# Power.net
KiCad netlist of a schematic drawn in Altium Designer
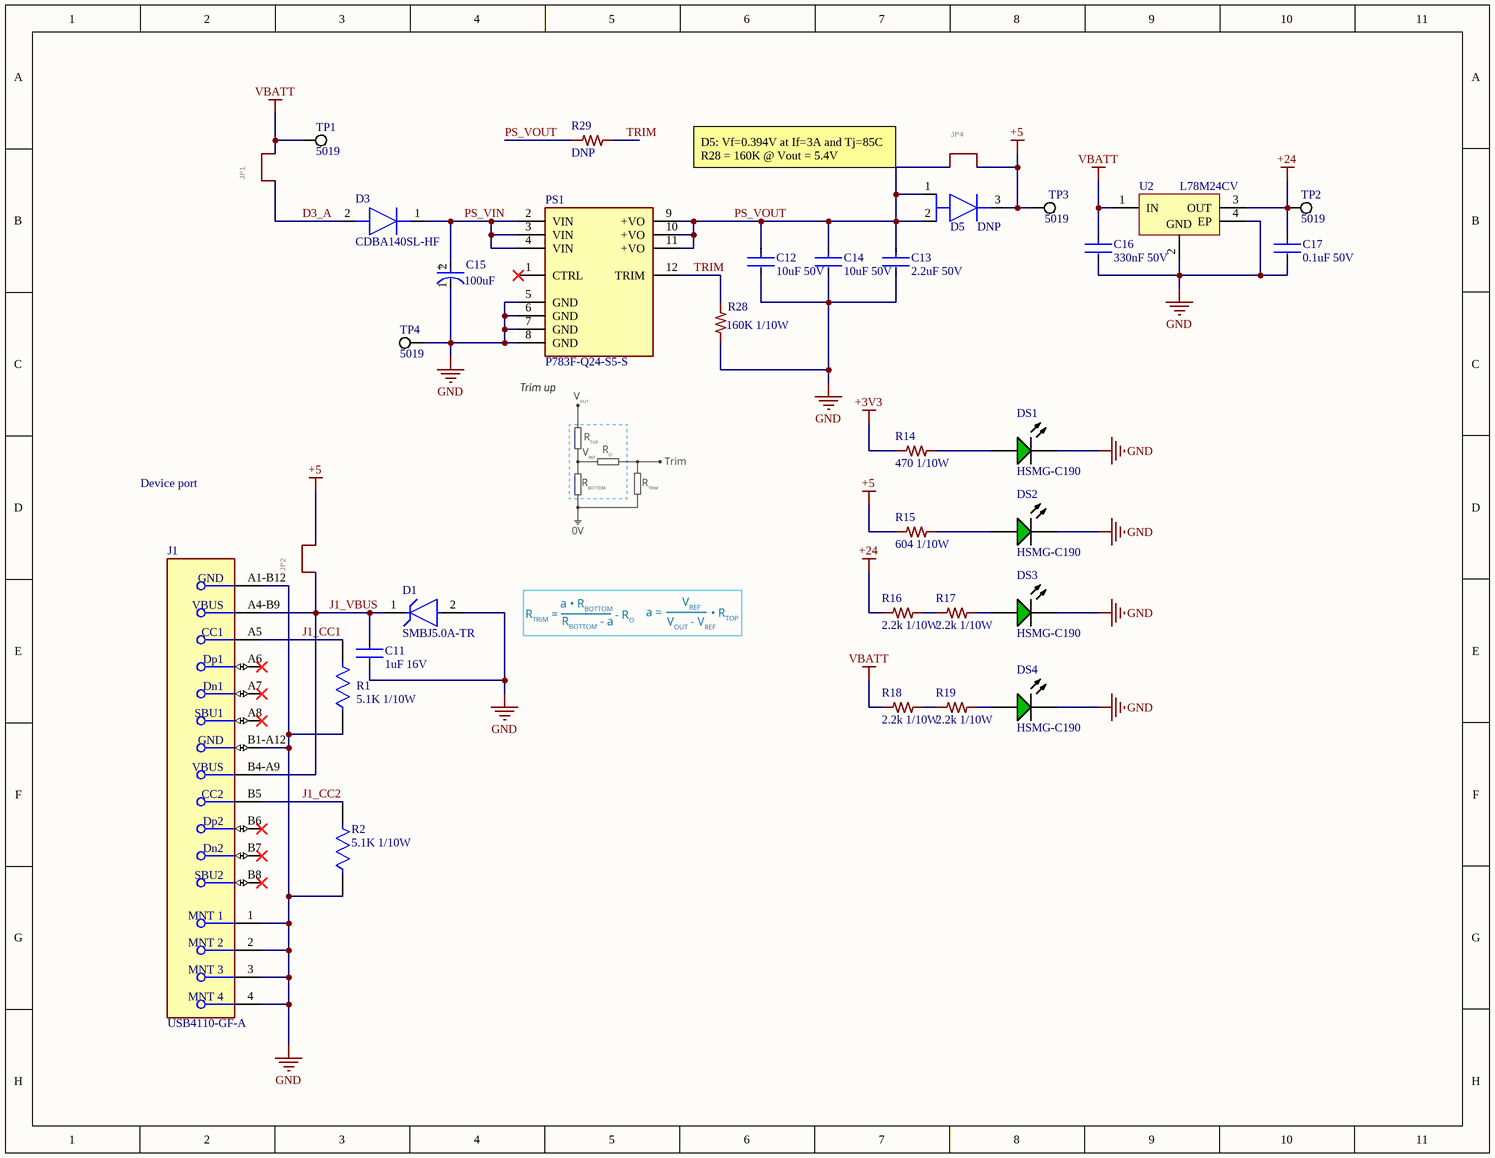
[diagram p0: Power.SchDoc]

(export (version "E")
  (design (tool "Eeschema 10.0.6"))
  (components
    (comp (ref "C11")
      (value "1uF 16V")
      (footprint "CAPACITOR_0603")
      (description "CAP CER 1UF 16V X5R 0603")
      (fields (field (name "MPN") "CL10A105KO8NNNC") (field (name "MFR") "Samsung Electro-Mechanics"))
      (libsource (lib "CM4") (part "CL10A105KO8NNNC"))
    )
    (comp (ref "C12")
      (value "10uF 50V")
      (footprint "FP-GRM21B-0_2-e0_2_0_7-IPC_A")
      (description "Chip Multilayer Ceramic Capacitors for General Purpose, 0805, 10uF, X5R, 15%, 10%, 50V")
      (fields (field (name "TOLERANCE") "10%") (field (name "MPN") "GRM21BR61H106KE43L"))
      (libsource (lib "Altium Content Vault") (part "b4654b650e69147ec39a6b967a45e02"))
    )
    (comp (ref "C13")
      (value "2.2uF 50V")
      (footprint "CAPACITOR_0603")
      (description "CAP CER 2.2UF 50V X5R 0603")
      (fields (field (name "TOLERANCE") "10%") (field (name "MPN") "GRT188R61H225KE13D"))
      (libsource (lib "CM4") (part "GRT188R61H225KE13D"))
    )
    (comp (ref "C14")
      (value "10uF 50V")
      (footprint "FP-GRM21B-0_2-e0_2_0_7-IPC_A")
      (description "Chip Multilayer Ceramic Capacitors for General Purpose, 0805, 10uF, X5R, 15%, 10%, 50V")
      (fields (field (name "TOLERANCE") "10%") (field (name "MPN") "GRM21BR61H106KE43L"))
      (libsource (lib "Altium Content Vault") (part "b4654b650e69147ec39a6b967a45e02"))
    )
    (comp (ref "C15")
      (value "UWT1H101MNL1GS")
      (footprint "FP-UWT1H101MNL1GS-MFG")
      (description "CAP ALUM 100UF 20% 50V SMD")
      (fields
        (field (name "TOLERANCE") "20%")
        (field (name "CAPACITANCE") "100uF")
        (field (name "VOLTAGE") "50V")
      )
      (libsource (lib "Altium Content Vault") (part "203bc49f2ac43e59fd269a8c329ed05"))
    )
    (comp (ref "C16")
      (value "330nF 50V")
      (footprint "CAPACITOR_0603")
      (description "CAP CER 0.33UF 50V X7R 0603")
      (fields (field (name "TOLERANCE") "10%") (field (name "VOLTAGE") "50V"))
      (libsource (lib "CM4") (part "C1608X7R1H334K080AC"))
    )
    (comp (ref "C17")
      (value "0.1uF 50V")
      (footprint "CAPACITOR_0603")
      (description "CAP CER 0.1UF 50V X7R 0603")
      (fields (field (name "MPN") "CL10B104KB8NNWC") (field (name "MFR") "Samsung Electro-Mechanics"))
      (libsource (lib "CM4") (part "CL10B104KB8NNWC"))
    )
    (comp (ref "D1")
      (value "SMBJ5.0A-TR")
      (footprint "FP-SMB-MFG")
      (description "TVS DIODE 5V 13.4V SMB")
      (fields
        (field (name "MFR") "STMicroelectronics")
        (field (name "OCTOPART") "https://octopart.com/smbj5.0a-tr-stmicroelectronics-347079")
      )
      (libsource (lib "CM4") (part "SMBJ5.0A-TR"))
    )
    (comp (ref "D3")
      (value "CDBA140SL-HF")
      (footprint "DIOM5225X250N")
      (description "DIODE SCHOTTKY 40V 1.4A DO214AC")
      (fields
        (field (name "MOUSER PART NUMBER") "750-CDBA140SL-HF")
        (field (name "MFR") "Comchip Technology")
      )
      (libsource (lib "CM4") (part "CDBA140SL-HF"))
    )
    (comp (ref "D5")
      (value "PMEG045T050EPDZ")
      (footprint "PMEG060V100EPDZ")
      (description "DIODE SCHOTTKY 45V 5A CFP15")
      (fields (field (name "DNP") "DNP") (field (name "MFR") "Nexperia USA Inc."))
      (libsource (lib "CM4") (part "PMEG045T050EPDZ"))
    )
    (comp (ref "DS1")
      (value "HSMG-C190")
      (footprint "AVAG-HSMX-C190_V")
      (description "Chip LED, Green, 2.2 V, -40 to 85 degC, 2-Pin SMD, RoHS, Tape and Reel")
      (fields (field (name "MFR") "Broadcom Limited"))
      (libsource (lib "CM4") (part "HSMG-C190"))
    )
    (comp (ref "DS2")
      (value "HSMG-C190")
      (footprint "AVAG-HSMX-C190_V")
      (description "Chip LED, Green, 2.2 V, -40 to 85 degC, 2-Pin SMD, RoHS, Tape and Reel")
      (fields (field (name "MFR") "Broadcom Limited"))
      (libsource (lib "CM4") (part "HSMG-C190"))
    )
    (comp (ref "DS3")
      (value "HSMG-C190")
      (footprint "AVAG-HSMX-C190_V")
      (description "Chip LED, Green, 2.2 V, -40 to 85 degC, 2-Pin SMD, RoHS, Tape and Reel")
      (fields (field (name "MFR") "Broadcom Limited"))
      (libsource (lib "CM4") (part "HSMG-C190"))
    )
    (comp (ref "DS4")
      (value "HSMG-C190")
      (footprint "AVAG-HSMX-C190_V")
      (description "Chip LED, Green, 2.2 V, -40 to 85 degC, 2-Pin SMD, RoHS, Tape and Reel")
      (fields (field (name "MFR") "Broadcom Limited"))
      (libsource (lib "CM4") (part "HSMG-C190"))
    )
    (comp (ref "J1")
      (value "USB4110-GF-A")
      (footprint "FP-USB4110-GF-A-MFG")
      (description "CONN USB 2.0 TYPE-C R/A SMT")
      (fields
        (field (name "OCTOPART") "https://octopart.com/usb4110-gf-a-gct-103941985")
        (field (name "MANUFACTURER") "GCT")
      )
      (libsource (lib "CM4") (part "USB4110-GF-A"))
    )
    (comp (ref "JP1")
      (value "TSM-102-01-L-SV")
      (footprint "FP-TSM-102-01-L-SV-P-TR-MFG")
      (description "CONN HEADER SMD 2POS 2.54MM")
      (fields (field (name "MANUFACTURER") "Samtec Inc."))
      (libsource (lib "CM4") (part "JUMPER_?_SMD_2POS"))
    )
    (comp (ref "JP2")
      (value "TSM-102-01-L-SV")
      (footprint "FP-TSM-102-01-L-SV-P-TR-MFG")
      (description "CONN HEADER SMD 2POS 2.54MM")
      (fields (field (name "MANUFACTURER") "Samtec Inc."))
      (libsource (lib "CM4") (part "JUMPER_?_SMD_2POS"))
    )
    (comp (ref "JP4")
      (value "CRCW12100000Z0EA")
      (footprint "FP-RMCF1210-IPC_B")
      (description "RES JUMPER SMD 0 OHM JUMPER 1/2W 1210")
      (fields (field (name "MANUFACTURER") "Vishay Dale"))
      (libsource (lib "CM4") (part "JUMPER_?_1210"))
    )
    (comp (ref "PS1")
      (value "P783F-Q24-S5-S")
      (footprint "CM4:CONV_P783F-Q24-S5-S")
      (description "DC DC CONVERTER 5V 15W")
      (fields (field (name "MFR") "CUI"))
      (libsource (lib "CM4") (part "P783F-Q24-S5-S"))
    )
    (comp (ref "R1")
      (value "5.1K 1/10W")
      (footprint "0603R")
      (description "RES SMD 5.1K OHM 0.1% 1/10W 0603")
      (fields (field (name "MFR") "Panasonic Electronic Components") (field (name "MPN") "ERA-3AEB512V"))
      (libsource (lib "CM4") (part "ERA-3AEB512V"))
    )
    (comp (ref "R2")
      (value "5.1K 1/10W")
      (footprint "0603R")
      (description "RES SMD 5.1K OHM 0.1% 1/10W 0603")
      (fields (field (name "MFR") "Panasonic Electronic Components") (field (name "MPN") "ERA-3AEB512V"))
      (libsource (lib "CM4") (part "ERA-3AEB512V"))
    )
    (comp (ref "R14")
      (value "470 1/10W")
      (footprint "0603R")
      (description "RES SMD 470 OHM 0.1% 1/10W 0603")
      (fields
        (field (name "MANUFACTURER") "Panasonic Electronic Components")
        (field (name "MPN") "ERA-3AEB471V")
      )
      (libsource (lib "CM4") (part "ERA-3AEB471V"))
    )
    (comp (ref "R15")
      (value "604 1/10W")
      (footprint "0603R")
      (description "RES SMD 604 OHM 1% 1/10W 0603")
      (fields (field (name "MANUFACTURER") "Stackpole Electronics Inc") (field (name "MPN") "RMCF0603FT604R"))
      (libsource (lib "CM4") (part "RMCF0603FT604R"))
    )
    (comp (ref "R16")
      (value "2.2k 1/10W")
      (footprint "0603R")
      (description "RES SMD 2.2K OHM 0.1% 1/10W 0603")
      (fields (field (name "MANUFACTURER") "YAGEO") (field (name "MPN") "RT0603BRD072K2L"))
      (libsource (lib "CM4") (part "RT0603BRD072K2L"))
    )
    (comp (ref "R17")
      (value "2.2k 1/10W")
      (footprint "0603R")
      (description "RES SMD 2.2K OHM 0.1% 1/10W 0603")
      (fields (field (name "MANUFACTURER") "YAGEO") (field (name "MPN") "RT0603BRD072K2L"))
      (libsource (lib "CM4") (part "RT0603BRD072K2L"))
    )
    (comp (ref "R18")
      (value "2.2k 1/10W")
      (footprint "0603R")
      (description "RES SMD 2.2K OHM 0.1% 1/10W 0603")
      (fields (field (name "MANUFACTURER") "YAGEO") (field (name "MPN") "RT0603BRD072K2L"))
      (libsource (lib "CM4") (part "RT0603BRD072K2L"))
    )
    (comp (ref "R19")
      (value "2.2k 1/10W")
      (footprint "0603R")
      (description "RES SMD 2.2K OHM 0.1% 1/10W 0603")
      (fields (field (name "MANUFACTURER") "YAGEO") (field (name "MPN") "RT0603BRD072K2L"))
      (libsource (lib "CM4") (part "RT0603BRD072K2L"))
    )
    (comp (ref "R28")
      (value "160K 1/10W")
      (footprint "0603R")
      (description "RES SMD 160K OHM 0.1% 1/10W 0603")
      (fields (field (name "MANUFACTURER") "Stackpole Electronics Inc") (field (name "MPN") "RMCF0603FT604R"))
      (libsource (lib "CM4") (part "RT0603BRD07160KL"))
    )
    (comp (ref "R29")
      (value "~")
      (footprint "0603R")
      (description "RES SMD CUSTOM 0603")
      (fields (field (name "DNP") "DNP"))
      (libsource (lib "CM4") (part "RESISTOR_0603"))
    )
    (comp (ref "TP1")
      (value "5019")
      (footprint "KSTN-5019_V")
      (description "Test Point, 1 Position SMD, RoHS, Tape and Reel")
      (fields (field (name "MFR") "Keystone Electronics"))
      (libsource (lib "CM4") (part "CMP-1672-00008-1"))
    )
    (comp (ref "TP2")
      (value "5019")
      (footprint "KSTN-5019_V")
      (description "Test Point, 1 Position SMD, RoHS, Tape and Reel")
      (fields (field (name "MFR") "Keystone Electronics"))
      (libsource (lib "CM4") (part "CMP-1672-00008-1"))
    )
    (comp (ref "TP3")
      (value "5019")
      (footprint "KSTN-5019_V")
      (description "Test Point, 1 Position SMD, RoHS, Tape and Reel")
      (fields (field (name "MFR") "Keystone Electronics"))
      (libsource (lib "CM4") (part "CMP-1672-00008-1"))
    )
    (comp (ref "TP4")
      (value "5019")
      (footprint "KSTN-5019_V")
      (description "Test Point, 1 Position SMD, RoHS, Tape and Reel")
      (fields (field (name "MFR") "Keystone Electronics"))
      (libsource (lib "CM4") (part "CMP-1672-00008-1"))
    )
    (comp (ref "U2")
      (value "L78M24CV")
      (footprint "TO-220")
      (description "Positive Voltage Regulator, 15V, 3-Pin TO-220")
      (fields (field (name "MFR") "STMicroelectronics"))
      (libsource (lib "CM4") (part "L78M24CV"))
    )
  )
  (nets
    (net (code "1") (name "+3V3") (class "Default")
      (node (ref "R14") (pin "1") (pinfunction "1_1") (pintype "passive"))
    )
    (net (code "2") (name "+5") (class "Default")
      (node (ref "D5") (pin "3") (pinfunction "K_3") (pintype "passive"))
      (node (ref "JP2") (pin "2") (pinfunction "2_2") (pintype "passive"))
      (node (ref "JP4") (pin "2") (pinfunction "2_2") (pintype "passive"))
      (node (ref "R15") (pin "1") (pinfunction "1_1") (pintype "passive"))
      (node (ref "TP3") (pin "1") (pinfunction "1_1") (pintype "passive"))
    )
    (net (code "3") (name "+24") (class "Default")
      (node (ref "C17") (pin "2") (pinfunction "2_2") (pintype "passive"))
      (node (ref "R16") (pin "1") (pinfunction "1_1") (pintype "passive"))
      (node (ref "TP2") (pin "1") (pinfunction "1_1") (pintype "passive"))
      (node (ref "U2") (pin "3") (pinfunction "OUT_3") (pintype "power_in"))
    )
    (net (code "4") (name "/D3_A") (class "Default")
      (node (ref "D3") (pin "2") (pinfunction "A_2") (pintype "passive"))
      (node (ref "JP1") (pin "1") (pinfunction "1_1") (pintype "passive"))
    )
    (net (code "5") (name "/J1_CC1") (class "Default")
      (node (ref "J1") (pin "A5") (pinfunction "CC1_A5") (pintype "power_in"))
      (node (ref "R1") (pin "2") (pinfunction "2_2") (pintype "passive"))
    )
    (net (code "6") (name "/J1_CC2") (class "Default")
      (node (ref "J1") (pin "B5") (pinfunction "CC2_B5") (pintype "power_in"))
      (node (ref "R2") (pin "2") (pinfunction "2_2") (pintype "passive"))
    )
    (net (code "7") (name "/J1_VBUS") (class "Default")
      (node (ref "C11") (pin "2") (pinfunction "2_2") (pintype "passive"))
      (node (ref "D1") (pin "1") (pinfunction "K_1") (pintype "passive"))
      (node (ref "J1") (pin "A4-B9") (pinfunction "VBUS_A4-B9") (pintype "power_in"))
      (node (ref "J1") (pin "B4-A9") (pinfunction "VBUS_B4-A9") (pintype "power_in"))
      (node (ref "JP2") (pin "1") (pinfunction "1_1") (pintype "passive"))
    )
    (net (code "8") (name "/PS_VIN") (class "Default")
      (node (ref "C15") (pin "2") (pinfunction "A_2") (pintype "passive"))
      (node (ref "D3") (pin "1") (pinfunction "K_1") (pintype "passive"))
      (node (ref "PS1") (pin "2") (pinfunction "VIN_2") (pintype "power_in"))
      (node (ref "PS1") (pin "3") (pinfunction "VIN_3") (pintype "power_in"))
      (node (ref "PS1") (pin "4") (pinfunction "VIN_4") (pintype "power_in"))
    )
    (net (code "9") (name "/PS_VOUT") (class "Default")
      (node (ref "C12") (pin "1") (pinfunction "1_1") (pintype "passive"))
      (node (ref "C13") (pin "1") (pinfunction "1_1") (pintype "passive"))
      (node (ref "C14") (pin "1") (pinfunction "1_1") (pintype "passive"))
      (node (ref "D5") (pin "1") (pinfunction "A_1") (pintype "passive"))
      (node (ref "D5") (pin "2") (pinfunction "A_2") (pintype "passive"))
      (node (ref "JP4") (pin "1") (pinfunction "1_1") (pintype "passive"))
      (node (ref "PS1") (pin "10") (pinfunction "+VO_10") (pintype "power_in"))
      (node (ref "PS1") (pin "11") (pinfunction "+VO_11") (pintype "power_in"))
      (node (ref "PS1") (pin "9") (pinfunction "+VO_9") (pintype "power_in"))
      (node (ref "R29") (pin "2") (pinfunction "2_2") (pintype "passive"))
    )
    (net (code "10") (name "/TRIM") (class "Default")
      (node (ref "PS1") (pin "12") (pinfunction "TRIM_12") (pintype "passive"))
      (node (ref "R28") (pin "2") (pinfunction "2_2") (pintype "passive"))
      (node (ref "R29") (pin "1") (pinfunction "1_1") (pintype "passive"))
    )
    (net (code "11") (name "GND") (class "Default")
      (node (ref "C11") (pin "1") (pinfunction "1_1") (pintype "passive"))
      (node (ref "C12") (pin "2") (pinfunction "2_2") (pintype "passive"))
      (node (ref "C13") (pin "2") (pinfunction "2_2") (pintype "passive"))
      (node (ref "C14") (pin "2") (pinfunction "2_2") (pintype "passive"))
      (node (ref "C15") (pin "1") (pinfunction "C_1") (pintype "passive"))
      (node (ref "C16") (pin "1") (pinfunction "1_1") (pintype "passive"))
      (node (ref "C17") (pin "1") (pinfunction "1_1") (pintype "passive"))
      (node (ref "D1") (pin "2") (pinfunction "A_2") (pintype "passive"))
      (node (ref "DS1") (pin "2") (pinfunction "K_2") (pintype "passive"))
      (node (ref "DS2") (pin "2") (pinfunction "K_2") (pintype "passive"))
      (node (ref "DS3") (pin "2") (pinfunction "K_2") (pintype "passive"))
      (node (ref "DS4") (pin "2") (pinfunction "K_2") (pintype "passive"))
      (node (ref "J1") (pin "1") (pinfunction "MNT_1_1") (pintype "passive"))
      (node (ref "J1") (pin "2") (pinfunction "MNT_2_2") (pintype "passive"))
      (node (ref "J1") (pin "3") (pinfunction "MNT_3_3") (pintype "passive"))
      (node (ref "J1") (pin "4") (pinfunction "MNT_4_4") (pintype "passive"))
      (node (ref "J1") (pin "A1-B12") (pinfunction "GND_A1-B12") (pintype "passive"))
      (node (ref "J1") (pin "B1-A12") (pinfunction "GND_B1-A12") (pintype "bidirectional"))
      (node (ref "PS1") (pin "5") (pinfunction "GND_5") (pintype "power_in"))
      (node (ref "PS1") (pin "6") (pinfunction "GND_6") (pintype "power_in"))
      (node (ref "PS1") (pin "7") (pinfunction "GND_7") (pintype "power_in"))
      (node (ref "PS1") (pin "8") (pinfunction "GND_8") (pintype "power_in"))
      (node (ref "R1") (pin "1") (pinfunction "1_1") (pintype "passive"))
      (node (ref "R2") (pin "1") (pinfunction "1_1") (pintype "passive"))
      (node (ref "R28") (pin "1") (pinfunction "1_1") (pintype "passive"))
      (node (ref "TP4") (pin "1") (pinfunction "1_1") (pintype "passive"))
      (node (ref "U2") (pin "2") (pinfunction "GND_2") (pintype "power_in"))
      (node (ref "U2") (pin "4") (pinfunction "EP_4") (pintype "power_in"))
    )
    (net (code "12") (name "Net-(DS1-A)") (class "Default")
      (node (ref "DS1") (pin "1") (pinfunction "A_1") (pintype "passive"))
      (node (ref "R14") (pin "2") (pinfunction "2_2") (pintype "passive"))
    )
    (net (code "13") (name "Net-(DS2-A)") (class "Default")
      (node (ref "DS2") (pin "1") (pinfunction "A_1") (pintype "passive"))
      (node (ref "R15") (pin "2") (pinfunction "2_2") (pintype "passive"))
    )
    (net (code "14") (name "Net-(DS3-A)") (class "Default")
      (node (ref "DS3") (pin "1") (pinfunction "A_1") (pintype "passive"))
      (node (ref "R17") (pin "2") (pinfunction "2_2") (pintype "passive"))
    )
    (net (code "15") (name "Net-(DS4-A)") (class "Default")
      (node (ref "DS4") (pin "1") (pinfunction "A_1") (pintype "passive"))
      (node (ref "R19") (pin "2") (pinfunction "2_2") (pintype "passive"))
    )
    (net (code "16") (name "Net-(R16-Pad2)") (class "Default")
      (node (ref "R16") (pin "2") (pinfunction "2_2") (pintype "passive"))
      (node (ref "R17") (pin "1") (pinfunction "1_1") (pintype "passive"))
    )
    (net (code "17") (name "Net-(R18-Pad2)") (class "Default")
      (node (ref "R18") (pin "2") (pinfunction "2_2") (pintype "passive"))
      (node (ref "R19") (pin "1") (pinfunction "1_1") (pintype "passive"))
    )
    (net (code "18") (name "VBATT") (class "Default")
      (node (ref "C16") (pin "2") (pinfunction "2_2") (pintype "passive"))
      (node (ref "JP1") (pin "2") (pinfunction "2_2") (pintype "passive"))
      (node (ref "R18") (pin "1") (pinfunction "1_1") (pintype "passive"))
      (node (ref "TP1") (pin "1") (pinfunction "1_1") (pintype "passive"))
      (node (ref "U2") (pin "1") (pinfunction "IN_1") (pintype "power_in"))
    )
    (net (code "19") (name "unconnected-(J1-Dn1-PadA7)") (class "Default")
      (node (ref "J1") (pin "A7") (pinfunction "Dn1_A7") (pintype "bidirectional+no_connect"))
    )
    (net (code "20") (name "unconnected-(J1-Dn2-PadB7)") (class "Default")
      (node (ref "J1") (pin "B7") (pinfunction "Dn2_B7") (pintype "bidirectional+no_connect"))
    )
    (net (code "21") (name "unconnected-(J1-Dp1-PadA6)") (class "Default")
      (node (ref "J1") (pin "A6") (pinfunction "Dp1_A6") (pintype "bidirectional+no_connect"))
    )
    (net (code "22") (name "unconnected-(J1-Dp2-PadB6)") (class "Default")
      (node (ref "J1") (pin "B6") (pinfunction "Dp2_B6") (pintype "bidirectional+no_connect"))
    )
    (net (code "23") (name "unconnected-(J1-SBU1-PadA8)") (class "Default")
      (node (ref "J1") (pin "A8") (pinfunction "SBU1_A8") (pintype "bidirectional+no_connect"))
    )
    (net (code "24") (name "unconnected-(J1-SBU2-PadB8)") (class "Default")
      (node (ref "J1") (pin "B8") (pinfunction "SBU2_B8") (pintype "bidirectional+no_connect"))
    )
    (net (code "25") (name "unconnected-(PS1-CTRL-Pad1)") (class "Default")
      (node (ref "PS1") (pin "1") (pinfunction "CTRL_1") (pintype "power_in+no_connect"))
    )
  )
)
